# InterfacesB_NONISO232b.net
KiCad netlist of a schematic drawn in Altium Designer
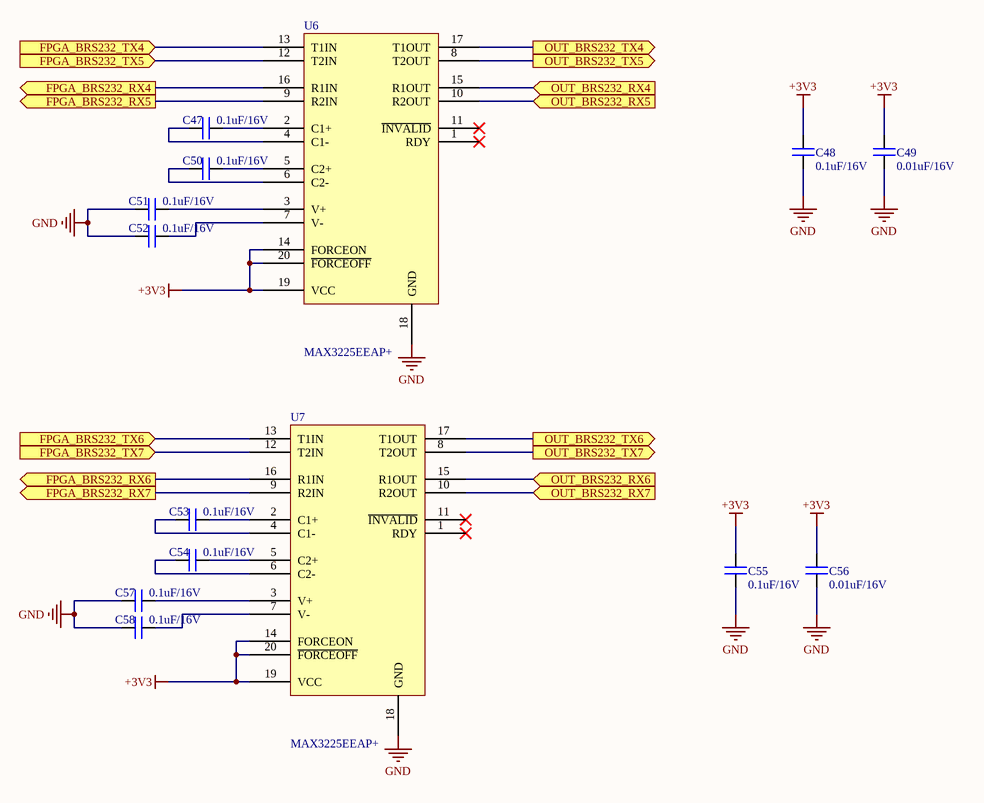
[diagram p0: InterfacesB_NONISO232b.SchDoc]

(export (version "E")
  (design (tool "Eeschema 10.0.6"))
  (components
    (comp (ref "C47")
      (value "0.1uF/16V")
      (footprint "CAP_0805")
      (fields (field (name "Comment") "CAP_0805"))
      (libsource (lib "AdapterLib") (part "CAP_0805"))
    )
    (comp (ref "C48")
      (value "0.1uF/16V")
      (footprint "CAP_0805")
      (fields (field (name "Comment") "CAP_0805"))
      (libsource (lib "AdapterLib") (part "CAP_0805"))
    )
    (comp (ref "C49")
      (value "0.01uF/16V")
      (footprint "CAP_0805")
      (fields (field (name "Comment") "CAP_0805"))
      (libsource (lib "AdapterLib") (part "CAP_0805"))
    )
    (comp (ref "C50")
      (value "0.1uF/16V")
      (footprint "CAP_0805")
      (fields (field (name "Comment") "CAP_0805"))
      (libsource (lib "AdapterLib") (part "CAP_0805"))
    )
    (comp (ref "C51")
      (value "0.1uF/16V")
      (footprint "CAP_0805")
      (fields (field (name "Comment") "CAP_0805"))
      (libsource (lib "AdapterLib") (part "CAP_0805"))
    )
    (comp (ref "C52")
      (value "0.1uF/16V")
      (footprint "CAP_0805")
      (fields (field (name "Comment") "CAP_0805"))
      (libsource (lib "AdapterLib") (part "CAP_0805"))
    )
    (comp (ref "C53")
      (value "0.1uF/16V")
      (footprint "CAP_0805")
      (fields (field (name "Comment") "CAP_0805"))
      (libsource (lib "AdapterLib") (part "CAP_0805"))
    )
    (comp (ref "C54")
      (value "0.1uF/16V")
      (footprint "CAP_0805")
      (fields (field (name "Comment") "CAP_0805"))
      (libsource (lib "AdapterLib") (part "CAP_0805"))
    )
    (comp (ref "C55")
      (value "0.1uF/16V")
      (footprint "CAP_0805")
      (fields (field (name "Comment") "CAP_0805"))
      (libsource (lib "AdapterLib") (part "CAP_0805"))
    )
    (comp (ref "C56")
      (value "0.01uF/16V")
      (footprint "CAP_0805")
      (fields (field (name "Comment") "CAP_0805"))
      (libsource (lib "AdapterLib") (part "CAP_0805"))
    )
    (comp (ref "C57")
      (value "0.1uF/16V")
      (footprint "CAP_0805")
      (fields (field (name "Comment") "CAP_0805"))
      (libsource (lib "AdapterLib") (part "CAP_0805"))
    )
    (comp (ref "C58")
      (value "0.1uF/16V")
      (footprint "CAP_0805")
      (fields (field (name "Comment") "CAP_0805"))
      (libsource (lib "AdapterLib") (part "CAP_0805"))
    )
    (comp (ref "U6")
      (value "MAX3225EEAP+")
      (footprint "MAX3225EEAP+")
      (libsource (lib "AdapterLib") (part "MAX3225EEAP+"))
    )
    (comp (ref "U7")
      (value "MAX3225EEAP+")
      (footprint "MAX3225EEAP+")
      (libsource (lib "AdapterLib") (part "MAX3225EEAP+"))
    )
  )
  (nets
    (net (code "1") (name "+3V3") (class "Default")
      (node (ref "C48") (pin "1") (pinfunction "1_1") (pintype "passive"))
      (node (ref "C49") (pin "1") (pinfunction "1_1") (pintype "passive"))
      (node (ref "C55") (pin "1") (pinfunction "1_1") (pintype "passive"))
      (node (ref "C56") (pin "1") (pinfunction "1_1") (pintype "passive"))
      (node (ref "U6") (pin "14") (pinfunction "FORCEON_14") (pintype "passive"))
      (node (ref "U6") (pin "19") (pinfunction "VCC_19") (pintype "passive"))
      (node (ref "U6") (pin "20") (pinfunction "~{FORCEOFF}_20") (pintype "passive"))
      (node (ref "U7") (pin "14") (pinfunction "FORCEON_14") (pintype "passive"))
      (node (ref "U7") (pin "19") (pinfunction "VCC_19") (pintype "passive"))
      (node (ref "U7") (pin "20") (pinfunction "~{FORCEOFF}_20") (pintype "passive"))
    )
    (net (code "2") (name "/FPGA_BRS232_RX4") (class "Default")
      (node (ref "U6") (pin "16") (pinfunction "R1IN_16") (pintype "passive"))
    )
    (net (code "3") (name "/FPGA_BRS232_RX5") (class "Default")
      (node (ref "U6") (pin "9") (pinfunction "R2IN_9") (pintype "passive"))
    )
    (net (code "4") (name "/FPGA_BRS232_RX6") (class "Default")
      (node (ref "U7") (pin "16") (pinfunction "R1IN_16") (pintype "passive"))
    )
    (net (code "5") (name "/FPGA_BRS232_RX7") (class "Default")
      (node (ref "U7") (pin "9") (pinfunction "R2IN_9") (pintype "passive"))
    )
    (net (code "6") (name "/FPGA_BRS232_TX4") (class "Default")
      (node (ref "U6") (pin "13") (pinfunction "T1IN_13") (pintype "passive"))
    )
    (net (code "7") (name "/FPGA_BRS232_TX5") (class "Default")
      (node (ref "U6") (pin "12") (pinfunction "T2IN_12") (pintype "passive"))
    )
    (net (code "8") (name "/FPGA_BRS232_TX6") (class "Default")
      (node (ref "U7") (pin "13") (pinfunction "T1IN_13") (pintype "passive"))
    )
    (net (code "9") (name "/FPGA_BRS232_TX7") (class "Default")
      (node (ref "U7") (pin "12") (pinfunction "T2IN_12") (pintype "passive"))
    )
    (net (code "10") (name "/OUT_BRS232_RX4") (class "Default")
      (node (ref "U6") (pin "15") (pinfunction "R1OUT_15") (pintype "passive"))
    )
    (net (code "11") (name "/OUT_BRS232_RX5") (class "Default")
      (node (ref "U6") (pin "10") (pinfunction "R2OUT_10") (pintype "passive"))
    )
    (net (code "12") (name "/OUT_BRS232_RX6") (class "Default")
      (node (ref "U7") (pin "15") (pinfunction "R1OUT_15") (pintype "passive"))
    )
    (net (code "13") (name "/OUT_BRS232_RX7") (class "Default")
      (node (ref "U7") (pin "10") (pinfunction "R2OUT_10") (pintype "passive"))
    )
    (net (code "14") (name "/OUT_BRS232_TX4") (class "Default")
      (node (ref "U6") (pin "17") (pinfunction "T1OUT_17") (pintype "passive"))
    )
    (net (code "15") (name "/OUT_BRS232_TX5") (class "Default")
      (node (ref "U6") (pin "8") (pinfunction "T2OUT_8") (pintype "passive"))
    )
    (net (code "16") (name "/OUT_BRS232_TX6") (class "Default")
      (node (ref "U7") (pin "17") (pinfunction "T1OUT_17") (pintype "passive"))
    )
    (net (code "17") (name "/OUT_BRS232_TX7") (class "Default")
      (node (ref "U7") (pin "8") (pinfunction "T2OUT_8") (pintype "passive"))
    )
    (net (code "18") (name "GND") (class "Default")
      (node (ref "C48") (pin "2") (pinfunction "2_2") (pintype "passive"))
      (node (ref "C49") (pin "2") (pinfunction "2_2") (pintype "passive"))
      (node (ref "C51") (pin "2") (pinfunction "2_2") (pintype "passive"))
      (node (ref "C52") (pin "2") (pinfunction "2_2") (pintype "passive"))
      (node (ref "C55") (pin "2") (pinfunction "2_2") (pintype "passive"))
      (node (ref "C56") (pin "2") (pinfunction "2_2") (pintype "passive"))
      (node (ref "C57") (pin "2") (pinfunction "2_2") (pintype "passive"))
      (node (ref "C58") (pin "2") (pinfunction "2_2") (pintype "passive"))
      (node (ref "U6") (pin "18") (pinfunction "GND_18") (pintype "passive"))
      (node (ref "U7") (pin "18") (pinfunction "GND_18") (pintype "passive"))
    )
    (net (code "19") (name "Net-(U6-C1+)") (class "Default")
      (node (ref "C47") (pin "1") (pinfunction "1_1") (pintype "passive"))
      (node (ref "U6") (pin "2") (pinfunction "C1+_2") (pintype "passive"))
    )
    (net (code "20") (name "Net-(U6-C1-)") (class "Default")
      (node (ref "C47") (pin "2") (pinfunction "2_2") (pintype "passive"))
      (node (ref "U6") (pin "4") (pinfunction "C1-_4") (pintype "passive"))
    )
    (net (code "21") (name "Net-(U6-C2+)") (class "Default")
      (node (ref "C50") (pin "1") (pinfunction "1_1") (pintype "passive"))
      (node (ref "U6") (pin "5") (pinfunction "C2+_5") (pintype "passive"))
    )
    (net (code "22") (name "Net-(U6-C2-)") (class "Default")
      (node (ref "C50") (pin "2") (pinfunction "2_2") (pintype "passive"))
      (node (ref "U6") (pin "6") (pinfunction "C2-_6") (pintype "passive"))
    )
    (net (code "23") (name "Net-(U6-V+)") (class "Default")
      (node (ref "C51") (pin "1") (pinfunction "1_1") (pintype "passive"))
      (node (ref "U6") (pin "3") (pinfunction "V+_3") (pintype "passive"))
    )
    (net (code "24") (name "Net-(U6-V-)") (class "Default")
      (node (ref "C52") (pin "1") (pinfunction "1_1") (pintype "passive"))
      (node (ref "U6") (pin "7") (pinfunction "V-_7") (pintype "passive"))
    )
    (net (code "25") (name "Net-(U7-C1+)") (class "Default")
      (node (ref "C53") (pin "1") (pinfunction "1_1") (pintype "passive"))
      (node (ref "U7") (pin "2") (pinfunction "C1+_2") (pintype "passive"))
    )
    (net (code "26") (name "Net-(U7-C1-)") (class "Default")
      (node (ref "C53") (pin "2") (pinfunction "2_2") (pintype "passive"))
      (node (ref "U7") (pin "4") (pinfunction "C1-_4") (pintype "passive"))
    )
    (net (code "27") (name "Net-(U7-C2+)") (class "Default")
      (node (ref "C54") (pin "1") (pinfunction "1_1") (pintype "passive"))
      (node (ref "U7") (pin "5") (pinfunction "C2+_5") (pintype "passive"))
    )
    (net (code "28") (name "Net-(U7-C2-)") (class "Default")
      (node (ref "C54") (pin "2") (pinfunction "2_2") (pintype "passive"))
      (node (ref "U7") (pin "6") (pinfunction "C2-_6") (pintype "passive"))
    )
    (net (code "29") (name "Net-(U7-V+)") (class "Default")
      (node (ref "C57") (pin "1") (pinfunction "1_1") (pintype "passive"))
      (node (ref "U7") (pin "3") (pinfunction "V+_3") (pintype "passive"))
    )
    (net (code "30") (name "Net-(U7-V-)") (class "Default")
      (node (ref "C58") (pin "1") (pinfunction "1_1") (pintype "passive"))
      (node (ref "U7") (pin "7") (pinfunction "V-_7") (pintype "passive"))
    )
    (net (code "31") (name "unconnected-(U6-RDY-Pad1)") (class "Default")
      (node (ref "U6") (pin "1") (pinfunction "RDY_1") (pintype "passive+no_connect"))
    )
    (net (code "32") (name "unconnected-(U6-~{INVALID}-Pad11)") (class "Default")
      (node (ref "U6") (pin "11") (pinfunction "~{INVALID}_11") (pintype "passive+no_connect"))
    )
    (net (code "33") (name "unconnected-(U7-RDY-Pad1)") (class "Default")
      (node (ref "U7") (pin "1") (pinfunction "RDY_1") (pintype "passive+no_connect"))
    )
    (net (code "34") (name "unconnected-(U7-~{INVALID}-Pad11)") (class "Default")
      (node (ref "U7") (pin "11") (pinfunction "~{INVALID}_11") (pintype "passive+no_connect"))
    )
  )
)
